# Sheet1.net
KiCad netlist of a schematic drawn in Altium Designer
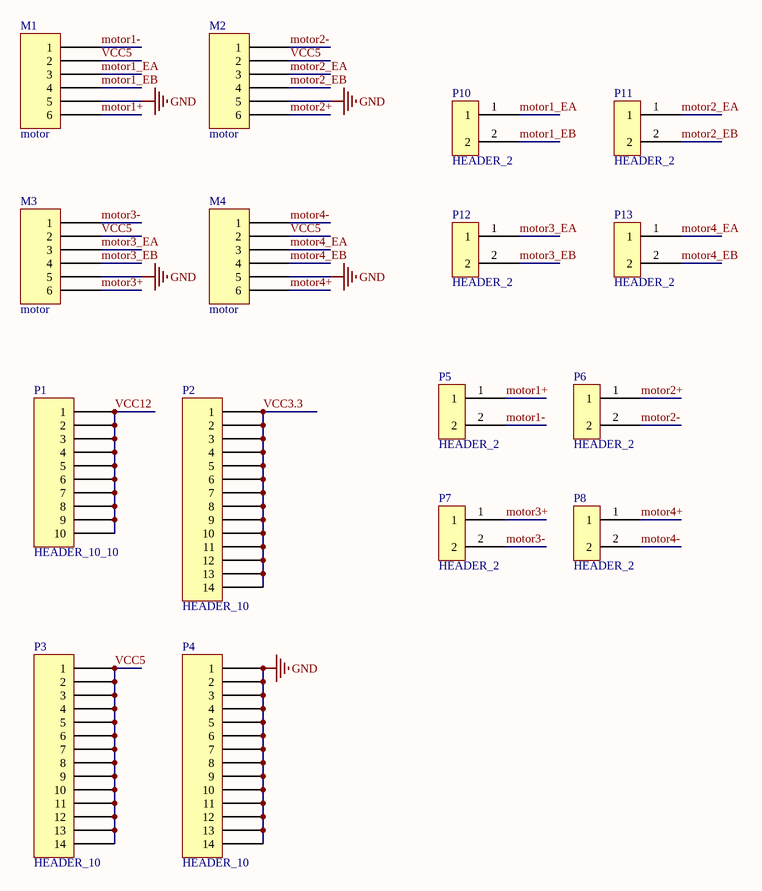
[diagram p0: Sheet1.SchDoc]

(export (version "E")
  (design (tool "Eeschema 10.0.6"))
  (components
    (comp (ref "M1") (value "motor") (footprint "Header6") (libsource (lib "Schlib1") (part "motor")))
    (comp (ref "M2") (value "motor") (footprint "Header6") (libsource (lib "Schlib1") (part "motor")))
    (comp (ref "M3") (value "motor") (footprint "Header6") (libsource (lib "Schlib1") (part "motor")))
    (comp (ref "M4") (value "motor") (footprint "Header6") (libsource (lib "Schlib1") (part "motor")))
    (comp (ref "P1")
      (value "HEADER_10_10")
      (footprint "HDR1X10_10")
      (libsource (lib "Schlib1") (part "HEADER_10_10"))
    )
    (comp (ref "P2") (value "HEADER_10") (footprint "HDR1X10") (libsource (lib "Schlib1") (part "HEADER_10")))
    (comp (ref "P3") (value "HEADER_10") (footprint "HDR1X10") (libsource (lib "Schlib1") (part "HEADER_10")))
    (comp (ref "P4") (value "HEADER_10") (footprint "HDR1X10") (libsource (lib "Schlib1") (part "HEADER_10")))
    (comp (ref "P5") (value "HEADER_2") (footprint "HDR1X2") (libsource (lib "Schlib1") (part "HEADER_2")))
    (comp (ref "P6") (value "HEADER_2") (footprint "HDR1X2") (libsource (lib "Schlib1") (part "HEADER_2")))
    (comp (ref "P7") (value "HEADER_2") (footprint "HDR1X2") (libsource (lib "Schlib1") (part "HEADER_2")))
    (comp (ref "P8") (value "HEADER_2") (footprint "HDR1X2") (libsource (lib "Schlib1") (part "HEADER_2")))
    (comp (ref "P10") (value "HEADER_2") (footprint "HDR1X2") (libsource (lib "Schlib1") (part "HEADER_2")))
    (comp (ref "P11") (value "HEADER_2") (footprint "HDR1X2") (libsource (lib "Schlib1") (part "HEADER_2")))
    (comp (ref "P12") (value "HEADER_2") (footprint "HDR1X2") (libsource (lib "Schlib1") (part "HEADER_2")))
    (comp (ref "P13") (value "HEADER_2") (footprint "HDR1X2") (libsource (lib "Schlib1") (part "HEADER_2")))
  )
  (nets
    (net (code "1") (name "/VCC3.3") (class "Default")
      (node (ref "P2") (pin "1") (pinfunction "1_1") (pintype "passive"))
      (node (ref "P2") (pin "10") (pinfunction "10_10") (pintype "passive"))
      (node (ref "P2") (pin "11") (pinfunction "11_11") (pintype "passive"))
      (node (ref "P2") (pin "12") (pinfunction "12_12") (pintype "passive"))
      (node (ref "P2") (pin "13") (pinfunction "13_13") (pintype "passive"))
      (node (ref "P2") (pin "14") (pinfunction "14_14") (pintype "passive"))
      (node (ref "P2") (pin "2") (pinfunction "2_2") (pintype "passive"))
      (node (ref "P2") (pin "3") (pinfunction "3_3") (pintype "passive"))
      (node (ref "P2") (pin "4") (pinfunction "4_4") (pintype "passive"))
      (node (ref "P2") (pin "5") (pinfunction "5_5") (pintype "passive"))
      (node (ref "P2") (pin "6") (pinfunction "6_6") (pintype "passive"))
      (node (ref "P2") (pin "7") (pinfunction "7_7") (pintype "passive"))
      (node (ref "P2") (pin "8") (pinfunction "8_8") (pintype "passive"))
      (node (ref "P2") (pin "9") (pinfunction "9_9") (pintype "passive"))
    )
    (net (code "2") (name "/VCC5") (class "Default")
      (node (ref "M1") (pin "2") (pinfunction "2_2") (pintype "passive"))
      (node (ref "M2") (pin "2") (pinfunction "2_2") (pintype "passive"))
      (node (ref "M3") (pin "2") (pinfunction "2_2") (pintype "passive"))
      (node (ref "M4") (pin "2") (pinfunction "2_2") (pintype "passive"))
      (node (ref "P3") (pin "1") (pinfunction "1_1") (pintype "passive"))
      (node (ref "P3") (pin "10") (pinfunction "10_10") (pintype "passive"))
      (node (ref "P3") (pin "11") (pinfunction "11_11") (pintype "passive"))
      (node (ref "P3") (pin "12") (pinfunction "12_12") (pintype "passive"))
      (node (ref "P3") (pin "13") (pinfunction "13_13") (pintype "passive"))
      (node (ref "P3") (pin "14") (pinfunction "14_14") (pintype "passive"))
      (node (ref "P3") (pin "2") (pinfunction "2_2") (pintype "passive"))
      (node (ref "P3") (pin "3") (pinfunction "3_3") (pintype "passive"))
      (node (ref "P3") (pin "4") (pinfunction "4_4") (pintype "passive"))
      (node (ref "P3") (pin "5") (pinfunction "5_5") (pintype "passive"))
      (node (ref "P3") (pin "6") (pinfunction "6_6") (pintype "passive"))
      (node (ref "P3") (pin "7") (pinfunction "7_7") (pintype "passive"))
      (node (ref "P3") (pin "8") (pinfunction "8_8") (pintype "passive"))
      (node (ref "P3") (pin "9") (pinfunction "9_9") (pintype "passive"))
    )
    (net (code "3") (name "/VCC12") (class "Default")
      (node (ref "P1") (pin "1") (pinfunction "1_1") (pintype "passive"))
      (node (ref "P1") (pin "10") (pinfunction "10_10") (pintype "passive"))
      (node (ref "P1") (pin "2") (pinfunction "2_2") (pintype "passive"))
      (node (ref "P1") (pin "3") (pinfunction "3_3") (pintype "passive"))
      (node (ref "P1") (pin "4") (pinfunction "4_4") (pintype "passive"))
      (node (ref "P1") (pin "5") (pinfunction "5_5") (pintype "passive"))
      (node (ref "P1") (pin "6") (pinfunction "6_6") (pintype "passive"))
      (node (ref "P1") (pin "7") (pinfunction "7_7") (pintype "passive"))
      (node (ref "P1") (pin "8") (pinfunction "8_8") (pintype "passive"))
      (node (ref "P1") (pin "9") (pinfunction "9_9") (pintype "passive"))
    )
    (net (code "4") (name "/motor1+") (class "Default")
      (node (ref "M1") (pin "6") (pinfunction "6_6") (pintype "passive"))
      (node (ref "P5") (pin "1") (pinfunction "1_1") (pintype "passive"))
    )
    (net (code "5") (name "/motor1-") (class "Default")
      (node (ref "M1") (pin "1") (pinfunction "1_1") (pintype "passive"))
      (node (ref "P5") (pin "2") (pinfunction "2_2") (pintype "passive"))
    )
    (net (code "6") (name "/motor1_EA") (class "Default")
      (node (ref "M1") (pin "3") (pinfunction "3_3") (pintype "passive"))
      (node (ref "P10") (pin "1") (pinfunction "1_1") (pintype "passive"))
    )
    (net (code "7") (name "/motor1_EB") (class "Default")
      (node (ref "M1") (pin "4") (pinfunction "4_4") (pintype "passive"))
      (node (ref "P10") (pin "2") (pinfunction "2_2") (pintype "passive"))
    )
    (net (code "8") (name "/motor2+") (class "Default")
      (node (ref "M2") (pin "6") (pinfunction "6_6") (pintype "passive"))
      (node (ref "P6") (pin "1") (pinfunction "1_1") (pintype "passive"))
    )
    (net (code "9") (name "/motor2-") (class "Default")
      (node (ref "M2") (pin "1") (pinfunction "1_1") (pintype "passive"))
      (node (ref "P6") (pin "2") (pinfunction "2_2") (pintype "passive"))
    )
    (net (code "10") (name "/motor2_EA") (class "Default")
      (node (ref "M2") (pin "3") (pinfunction "3_3") (pintype "passive"))
      (node (ref "P11") (pin "1") (pinfunction "1_1") (pintype "passive"))
    )
    (net (code "11") (name "/motor2_EB") (class "Default")
      (node (ref "M2") (pin "4") (pinfunction "4_4") (pintype "passive"))
      (node (ref "P11") (pin "2") (pinfunction "2_2") (pintype "passive"))
    )
    (net (code "12") (name "/motor3+") (class "Default")
      (node (ref "M3") (pin "6") (pinfunction "6_6") (pintype "passive"))
      (node (ref "P7") (pin "1") (pinfunction "1_1") (pintype "passive"))
    )
    (net (code "13") (name "/motor3-") (class "Default")
      (node (ref "M3") (pin "1") (pinfunction "1_1") (pintype "passive"))
      (node (ref "P7") (pin "2") (pinfunction "2_2") (pintype "passive"))
    )
    (net (code "14") (name "/motor3_EA") (class "Default")
      (node (ref "M3") (pin "3") (pinfunction "3_3") (pintype "passive"))
      (node (ref "P12") (pin "1") (pinfunction "1_1") (pintype "passive"))
    )
    (net (code "15") (name "/motor3_EB") (class "Default")
      (node (ref "M3") (pin "4") (pinfunction "4_4") (pintype "passive"))
      (node (ref "P12") (pin "2") (pinfunction "2_2") (pintype "passive"))
    )
    (net (code "16") (name "/motor4+") (class "Default")
      (node (ref "M4") (pin "6") (pinfunction "6_6") (pintype "passive"))
      (node (ref "P8") (pin "1") (pinfunction "1_1") (pintype "passive"))
    )
    (net (code "17") (name "/motor4-") (class "Default")
      (node (ref "M4") (pin "1") (pinfunction "1_1") (pintype "passive"))
      (node (ref "P8") (pin "2") (pinfunction "2_2") (pintype "passive"))
    )
    (net (code "18") (name "/motor4_EA") (class "Default")
      (node (ref "M4") (pin "3") (pinfunction "3_3") (pintype "passive"))
      (node (ref "P13") (pin "1") (pinfunction "1_1") (pintype "passive"))
    )
    (net (code "19") (name "/motor4_EB") (class "Default")
      (node (ref "M4") (pin "4") (pinfunction "4_4") (pintype "passive"))
      (node (ref "P13") (pin "2") (pinfunction "2_2") (pintype "passive"))
    )
    (net (code "20") (name "GND") (class "Default")
      (node (ref "M1") (pin "5") (pinfunction "5_5") (pintype "passive"))
      (node (ref "M2") (pin "5") (pinfunction "5_5") (pintype "passive"))
      (node (ref "M3") (pin "5") (pinfunction "5_5") (pintype "passive"))
      (node (ref "M4") (pin "5") (pinfunction "5_5") (pintype "passive"))
      (node (ref "P4") (pin "1") (pinfunction "1_1") (pintype "passive"))
      (node (ref "P4") (pin "10") (pinfunction "10_10") (pintype "passive"))
      (node (ref "P4") (pin "11") (pinfunction "11_11") (pintype "passive"))
      (node (ref "P4") (pin "12") (pinfunction "12_12") (pintype "passive"))
      (node (ref "P4") (pin "13") (pinfunction "13_13") (pintype "passive"))
      (node (ref "P4") (pin "14") (pinfunction "14_14") (pintype "passive"))
      (node (ref "P4") (pin "2") (pinfunction "2_2") (pintype "passive"))
      (node (ref "P4") (pin "3") (pinfunction "3_3") (pintype "passive"))
      (node (ref "P4") (pin "4") (pinfunction "4_4") (pintype "passive"))
      (node (ref "P4") (pin "5") (pinfunction "5_5") (pintype "passive"))
      (node (ref "P4") (pin "6") (pinfunction "6_6") (pintype "passive"))
      (node (ref "P4") (pin "7") (pinfunction "7_7") (pintype "passive"))
      (node (ref "P4") (pin "8") (pinfunction "8_8") (pintype "passive"))
      (node (ref "P4") (pin "9") (pinfunction "9_9") (pintype "passive"))
    )
  )
)
